# SolderingStation_Control.net
KiCad netlist of a schematic drawn in Altium Designer
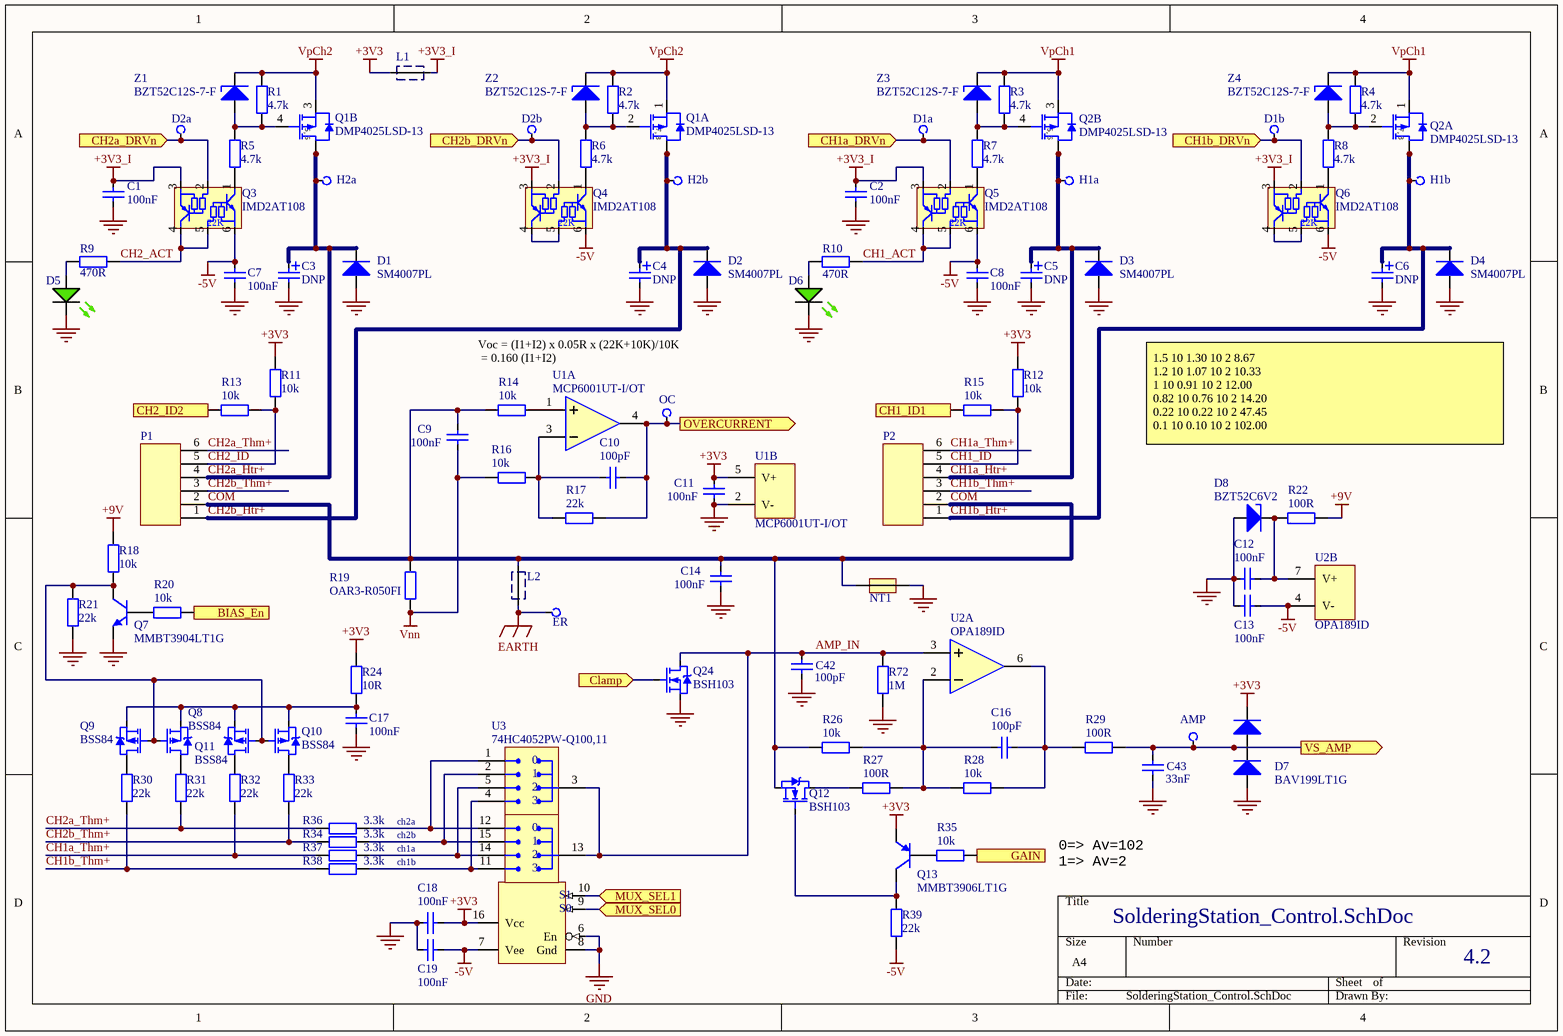
[diagram p0: SolderingStation_Control.SchDoc]

(export (version "E")
  (design (tool "Eeschema 10.0.6"))
  (components
    (comp (ref "AMP")
      (value "NTC1")
      (footprint "PCBPIN - 0.9mm")
      (description "Test Point")
      (libsource (lib "") (part "TP_1"))
    )
    (comp (ref "C1")
      (value "100nF")
      (footprint "CCNP1608-0603_N")
      (description "Capacitor non-polar SMT 0603")
      (fields
        (field (name "MANUFACTURER") "Generic Components")
        (field (name "PUBLISHER") "Altium Hobart Technology Centre")
      )
      (libsource (lib "MyLibrary") (part "Cap_CCNP_0603_100nF"))
    )
    (comp (ref "C2")
      (value "100nF")
      (footprint "CCNP1608-0603_N")
      (description "Capacitor non-polar SMT 0603")
      (fields
        (field (name "MANUFACTURER") "Generic Components")
        (field (name "PUBLISHER") "Altium Hobart Technology Centre")
      )
      (libsource (lib "MyLibrary") (part "Cap_CCNP_0603_100nF"))
    )
    (comp (ref "C3")
      (value "DNP")
      (footprint "CC2012-0805")
      (description "Capacitor SMT 0805")
      (fields
        (field (name "MANUFACTURER") "Generic Components")
        (field (name "PUBLISHER") "Altium Hobart Technology Centre")
      )
      (libsource (lib "MyLibrary") (part "Cap_CC_0805"))
    )
    (comp (ref "C4")
      (value "DNP")
      (footprint "CC2012-0805")
      (description "Capacitor SMT 0805")
      (fields
        (field (name "MANUFACTURER") "Generic Components")
        (field (name "PUBLISHER") "Altium Hobart Technology Centre")
      )
      (libsource (lib "MyLibrary") (part "Cap_CC_0805"))
    )
    (comp (ref "C5")
      (value "DNP")
      (footprint "CC2012-0805")
      (description "Capacitor SMT 0805")
      (fields
        (field (name "MANUFACTURER") "Generic Components")
        (field (name "PUBLISHER") "Altium Hobart Technology Centre")
      )
      (libsource (lib "MyLibrary") (part "Cap_CC_0805"))
    )
    (comp (ref "C6")
      (value "DNP")
      (footprint "CC2012-0805")
      (description "Capacitor SMT 0805")
      (fields
        (field (name "MANUFACTURER") "Generic Components")
        (field (name "PUBLISHER") "Altium Hobart Technology Centre")
      )
      (libsource (lib "MyLibrary") (part "Cap_CC_0805"))
    )
    (comp (ref "C7")
      (value "100nF")
      (footprint "CCNP1608-0603_N")
      (description "Capacitor non-polar SMT 0603")
      (fields
        (field (name "MANUFACTURER") "Generic Components")
        (field (name "PUBLISHER") "Altium Hobart Technology Centre")
      )
      (libsource (lib "MyLibrary") (part "Cap_CCNP_0603_100nF"))
    )
    (comp (ref "C8")
      (value "100nF")
      (footprint "CCNP1608-0603_N")
      (description "Capacitor non-polar SMT 0603")
      (fields
        (field (name "MANUFACTURER") "Generic Components")
        (field (name "PUBLISHER") "Altium Hobart Technology Centre")
      )
      (libsource (lib "MyLibrary") (part "Cap_CCNP_0603_100nF"))
    )
    (comp (ref "C9")
      (value "100nF")
      (footprint "CCNP1608-0603_N")
      (description "Capacitor non-polar SMT 0603")
      (fields
        (field (name "MANUFACTURER") "Generic Components")
        (field (name "PUBLISHER") "Altium Hobart Technology Centre")
      )
      (libsource (lib "MyLibrary") (part "Cap_CCNP_0603_100nF"))
    )
    (comp (ref "C10")
      (value "100pF")
      (footprint "CCNP1608-0603_N")
      (description "Capacitor non-polar SMT 0603")
      (fields
        (field (name "MANUFACTURER") "Generic Components")
        (field (name "PUBLISHER") "Altium Hobart Technology Centre")
      )
      (libsource (lib "MyLibrary") (part "Cap_CCNP_0603_100pF"))
    )
    (comp (ref "C11")
      (value "100nF")
      (footprint "CCNP1608-0603_N")
      (description "Capacitor non-polar SMT 0603")
      (fields
        (field (name "MANUFACTURER") "Generic Components")
        (field (name "PUBLISHER") "Altium Hobart Technology Centre")
      )
      (libsource (lib "MyLibrary") (part "Cap_CCNP_0603_100nF"))
    )
    (comp (ref "C12")
      (value "100nF")
      (footprint "CCNP1608-0603_N")
      (description "Capacitor non-polar SMT 0603")
      (fields
        (field (name "MANUFACTURER") "Generic Components")
        (field (name "PUBLISHER") "Altium Hobart Technology Centre")
      )
      (libsource (lib "MyLibrary") (part "Cap_CCNP_0603_100nF"))
    )
    (comp (ref "C13")
      (value "100nF")
      (footprint "CCNP1608-0603_N")
      (description "Capacitor non-polar SMT 0603")
      (fields
        (field (name "MANUFACTURER") "Generic Components")
        (field (name "PUBLISHER") "Altium Hobart Technology Centre")
      )
      (libsource (lib "MyLibrary") (part "Cap_CCNP_0603_100nF"))
    )
    (comp (ref "C14")
      (value "100nF")
      (footprint "CCNP1608-0603_N")
      (description "Capacitor non-polar SMT 0603")
      (fields
        (field (name "MANUFACTURER") "Generic Components")
        (field (name "PUBLISHER") "Altium Hobart Technology Centre")
      )
      (libsource (lib "MyLibrary") (part "Cap_CCNP_0603_100nF"))
    )
    (comp (ref "C16")
      (value "100pF")
      (footprint "CCNP1608-0603_N")
      (description "Capacitor non-polar SMT 0603")
      (fields
        (field (name "MANUFACTURER") "Generic Components")
        (field (name "PUBLISHER") "Altium Hobart Technology Centre")
      )
      (libsource (lib "MyLibrary") (part "Cap_CCNP_0603_100pF"))
    )
    (comp (ref "C17")
      (value "100nF")
      (footprint "CCNP1608-0603_N")
      (description "Capacitor non-polar SMT 0603")
      (fields
        (field (name "MANUFACTURER") "Generic Components")
        (field (name "PUBLISHER") "Altium Hobart Technology Centre")
      )
      (libsource (lib "MyLibrary") (part "Cap_CCNP_0603_100nF"))
    )
    (comp (ref "C18")
      (value "100nF")
      (footprint "CCNP1608-0603_N")
      (description "Capacitor non-polar SMT 0603")
      (fields
        (field (name "MANUFACTURER") "Generic Components")
        (field (name "PUBLISHER") "Altium Hobart Technology Centre")
      )
      (libsource (lib "MyLibrary") (part "Cap_CCNP_0603_100nF"))
    )
    (comp (ref "C19")
      (value "100nF")
      (footprint "CCNP1608-0603_N")
      (description "Capacitor non-polar SMT 0603")
      (fields
        (field (name "MANUFACTURER") "Generic Components")
        (field (name "PUBLISHER") "Altium Hobart Technology Centre")
      )
      (libsource (lib "MyLibrary") (part "Cap_CCNP_0603_100nF"))
    )
    (comp (ref "C42")
      (value "100pF")
      (footprint "CCNP1608-0603_N")
      (description "Capacitor non-polar SMT 0603")
      (fields
        (field (name "MANUFACTURER") "Generic Components")
        (field (name "PUBLISHER") "Altium Hobart Technology Centre")
      )
      (libsource (lib "MyLibrary") (part "Cap_CCNP_0603_100pF"))
    )
    (comp (ref "C43")
      (value "33nF")
      (footprint "CCNP1608-0603_N")
      (description "Capacitor non-polar SMT 0603")
      (fields
        (field (name "MANUFACTURER") "Generic Components")
        (field (name "PUBLISHER") "Altium Hobart Technology Centre")
      )
      (libsource (lib "MyLibrary") (part "Cap_CCNP_0603_100pF"))
    )
    (comp (ref "D1")
      (value "SM4007PL")
      (footprint "SOD-123FL")
      (description "Diodes - General Purpose, 1kV 1A 1.1V 1A SOD-123FL")
      (libsource (lib "MyLibrary") (part "SM4007PL"))
    )
    (comp (ref "D1a")
      (value "Drive1")
      (footprint "PCBPIN - 0.9mm")
      (description "Test Point")
      (libsource (lib "") (part "TP_1"))
    )
    (comp (ref "D1b")
      (value "Drive2")
      (footprint "PCBPIN - 0.9mm")
      (description "Test Point")
      (libsource (lib "") (part "TP_1"))
    )
    (comp (ref "D2")
      (value "SM4007PL")
      (footprint "SOD-123FL")
      (description "Diodes - General Purpose, 1kV 1A 1.1V 1A SOD-123FL")
      (libsource (lib "MyLibrary") (part "SM4007PL"))
    )
    (comp (ref "D2a")
      (value "Drive2")
      (footprint "PCBPIN - 0.9mm")
      (description "Test Point")
      (libsource (lib "") (part "TP_1"))
    )
    (comp (ref "D2b")
      (value "Drive2")
      (footprint "PCBPIN - 0.9mm")
      (description "Test Point")
      (libsource (lib "") (part "TP_1"))
    )
    (comp (ref "D3")
      (value "SM4007PL")
      (footprint "SOD-123FL")
      (description "Diodes - General Purpose, 1kV 1A 1.1V 1A SOD-123FL")
      (libsource (lib "MyLibrary") (part "SM4007PL"))
    )
    (comp (ref "D4")
      (value "SM4007PL")
      (footprint "SOD-123FL")
      (description "Diodes - General Purpose, 1kV 1A 1.1V 1A SOD-123FL")
      (libsource (lib "MyLibrary") (part "SM4007PL"))
    )
    (comp (ref "D5")
      (value "LED")
      (footprint "LED3MM-GREEN - 10mm Proud")
      (description "3mm Green LED")
      (fields (field (name "MANUFACTURER") "Generic Components") (field (name "PUBLISHER") "Altium Limited"))
      (libsource (lib "MySchLib") (part "LED_3MM_GREEN"))
    )
    (comp (ref "D6")
      (value "LED")
      (footprint "LED3MM-GREEN - 10mm Proud")
      (description "3mm Green LED")
      (fields (field (name "MANUFACTURER") "Generic Components") (field (name "PUBLISHER") "Altium Limited"))
      (libsource (lib "MySchLib") (part "LED_3MM_GREEN"))
    )
    (comp (ref "D7")
      (value "BAV199LT1G")
      (footprint "SOT23_N")
      (description "Diode - Dual Series low-leakage switching, SOT-23")
      (libsource (lib "MyLibrary") (part "BAV199LT1G"))
    )
    (comp (ref "D8")
      (value "BZT52C6V2")
      (footprint "SOD-123")
      (description "Zener Single Diode, 6.2 V, 500 mW, SOD-123, 6 %, 2 Pins, 150 °C")
      (fields (field (name "MANUFACTURER") "DiodesIncorporated"))
      (libsource (lib "MyLibrary") (part "BZT52C6V2"))
    )
    (comp (ref "ER")
      (value "Gnd")
      (footprint "PCBPIN - 0.9mm")
      (description "Test Point")
      (libsource (lib "MySchLib") (part "TP"))
    )
    (comp (ref "H1a")
      (value "Heater1")
      (footprint "PCBPIN - 0.9mm")
      (description "Test Point")
      (libsource (lib "MySchLib") (part "TP"))
    )
    (comp (ref "H1b")
      (value "Heater2")
      (footprint "PCBPIN - 0.9mm")
      (description "Test Point")
      (libsource (lib "MySchLib") (part "TP"))
    )
    (comp (ref "H2a")
      (value "Heater2")
      (footprint "PCBPIN - 0.9mm")
      (description "Test Point")
      (libsource (lib "MySchLib") (part "TP"))
    )
    (comp (ref "H2b")
      (value "Heater2")
      (footprint "PCBPIN - 0.9mm")
      (description "Test Point")
      (libsource (lib "MySchLib") (part "TP"))
    )
    (comp (ref "L1")
      (value "Ferrite Bead 600R@100MHz")
      (footprint "FB2012-0805")
      (description "Ferrite Bead 600Ω @ 100MHz 1 500mA 300mΩ 0805")
      (libsource (lib "MySchLib") (part "Ferrite Bead 0805 600R"))
    )
    (comp (ref "L2")
      (value "Ferrite Bead 600R@100MHz")
      (footprint "FB2012-0805")
      (description "Ferrite Bead 600Ω @ 100MHz 1 500mA 300mΩ 0805")
      (libsource (lib "MySchLib") (part "Ferrite Bead 0805 600R"))
    )
    (comp (ref "NT1")
      (value "NetTieVia")
      (footprint "NetTieVia")
      (libsource (lib "MyLibrary") (part "NetTieVia"))
    )
    (comp (ref "OC")
      (value "Overcurrent")
      (footprint "PCBPIN - 0.9mm")
      (description "Test Point")
      (libsource (lib "") (part "TP_1"))
    )
    (comp (ref "P1")
      (value "MOLEX-43045-0612")
      (footprint "MOLEX-43045-0612")
      (description "Wire-To-Board Connector, With Polarizing Peg, 3 mm, 6 Contacts, Header, Micro-Fit 3.0 43045 Series")
      (libsource (lib "MySchLib") (part "MOLEX-43045-0612"))
    )
    (comp (ref "P2")
      (value "MOLEX-43045-0612")
      (footprint "MOLEX-43045-0612")
      (description "Wire-To-Board Connector, With Polarizing Peg, 3 mm, 6 Contacts, Header, Micro-Fit 3.0 43045 Series")
      (libsource (lib "MySchLib") (part "MOLEX-43045-0612"))
    )
    (comp (ref "Q1")
      (value "DMP4025LSD-13")
      (footprint "SO-8_M")
      (description "P-Channel dual MOSFET, 40 V, 7.6 A, 0.018 ohm, SOIC, Surface Mount")
      (libsource (lib "MyLibrary") (part "DMP4025LSD-13"))
    )
    (comp (ref "Q2")
      (value "DMP4025LSD-13")
      (footprint "SO-8_M")
      (description "P-Channel dual MOSFET, 40 V, 7.6 A, 0.018 ohm, SOIC, Surface Mount")
      (libsource (lib "MyLibrary") (part "DMP4025LSD-13"))
    )
    (comp (ref "Q3")
      (value "IMD2AT108")
      (footprint "SOT457_M - MIRROR")
      (description "Pre-Biased NPN and PNP pair, 50 V, 100 mA, 22 kohm, 22 kohm")
      (libsource (lib "MySchLib") (part "IMD2AT108"))
    )
    (comp (ref "Q4")
      (value "IMD2AT108")
      (footprint "SOT457_M - MIRROR")
      (description "Pre-Biased NPN and PNP pair, 50 V, 100 mA, 22 kohm, 22 kohm")
      (libsource (lib "MySchLib") (part "IMD2AT108"))
    )
    (comp (ref "Q5")
      (value "IMD2AT108")
      (footprint "SOT457_M - MIRROR")
      (description "Pre-Biased NPN and PNP pair, 50 V, 100 mA, 22 kohm, 22 kohm")
      (libsource (lib "MySchLib") (part "IMD2AT108"))
    )
    (comp (ref "Q6")
      (value "IMD2AT108")
      (footprint "SOT457_M - MIRROR")
      (description "Pre-Biased NPN and PNP pair, 50 V, 100 mA, 22 kohm, 22 kohm")
      (libsource (lib "MySchLib") (part "IMD2AT108"))
    )
    (comp (ref "Q7")
      (value "MMBT3904LT1G")
      (footprint "SOT23_N")
      (description "General Purpose Transistor, NPN Silicon, 3-Pin SOT-23, Pb-Free, Tape and Reel")
      (fields (field (name "MANUFACTURER") "On Semiconductor"))
      (libsource (lib "MyLibrary") (part "MMBT3904LT1G"))
    )
    (comp (ref "Q8")
      (value "BSS84")
      (footprint "SOT23_M")
      (description "P-Channel Enhancement Mode FET -0.13 A, -50 V,  RDS(ON) = 10R at VGS = -5 V")
      (libsource (lib "MySchLib") (part "BSS84"))
    )
    (comp (ref "Q9")
      (value "BSS84")
      (footprint "SOT23_M")
      (description "P-Channel Enhancement Mode FET -0.13 A, -50 V,  RDS(ON) = 10R at VGS = -5 V")
      (libsource (lib "MySchLib") (part "BSS84"))
    )
    (comp (ref "Q10")
      (value "BSS84")
      (footprint "SOT23_M")
      (description "P-Channel Enhancement Mode FET -0.13 A, -50 V,  RDS(ON) = 10R at VGS = -5 V")
      (libsource (lib "MySchLib") (part "BSS84"))
    )
    (comp (ref "Q11")
      (value "BSS84")
      (footprint "SOT23_M")
      (description "P-Channel Enhancement Mode FET -0.13 A, -50 V,  RDS(ON) = 10R at VGS = -5 V")
      (libsource (lib "MySchLib") (part "BSS84"))
    )
    (comp (ref "Q12")
      (value "BSH103")
      (footprint "SOT23_N")
      (description "N-channel enhancement mode FET, , 30 V, 850 mA, 0.4 ohm, SOT23")
      (libsource (lib "MyLibrary") (part "BSH103"))
    )
    (comp (ref "Q13")
      (value "MMBT3906LT1G")
      (footprint "SOT23_N")
      (description "General Purpose Transistor, PNP Silicon, 3-Pin SOT-23, Pb-Free, Tape and Reel")
      (fields (field (name "MANUFACTURER") "On Semiconductor"))
      (libsource (lib "MyLibrary") (part "MMBT3906LT1G"))
    )
    (comp (ref "Q24")
      (value "BSH103")
      (footprint "SOT23_N")
      (description "N-channel enhancement mode FET, , 30 V, 850 mA, 0.4 ohm, SOT23")
      (libsource (lib "MyLibrary") (part "BSH103"))
    )
    (comp (ref "R1")
      (value "4.7k")
      (footprint "CR1608-0603_N")
      (description "Resistor SMT 0603")
      (fields
        (field (name "MANUFACTURER") "Generic Components")
        (field (name "PUBLISHER") "Altium Hobart Technology Centre")
      )
      (libsource (lib "MyLibrary") (part "Res_CR0603_4k7"))
    )
    (comp (ref "R2")
      (value "4.7k")
      (footprint "CR1608-0603_N")
      (description "Resistor SMT 0603")
      (fields
        (field (name "MANUFACTURER") "Generic Components")
        (field (name "PUBLISHER") "Altium Hobart Technology Centre")
      )
      (libsource (lib "MyLibrary") (part "Res_CR0603_4k7"))
    )
    (comp (ref "R3")
      (value "4.7k")
      (footprint "CR1608-0603_N")
      (description "Resistor SMT 0603")
      (fields
        (field (name "MANUFACTURER") "Generic Components")
        (field (name "PUBLISHER") "Altium Hobart Technology Centre")
      )
      (libsource (lib "MyLibrary") (part "Res_CR0603_4k7"))
    )
    (comp (ref "R4")
      (value "4.7k")
      (footprint "CR1608-0603_N")
      (description "Resistor SMT 0603")
      (fields
        (field (name "MANUFACTURER") "Generic Components")
        (field (name "PUBLISHER") "Altium Hobart Technology Centre")
      )
      (libsource (lib "MyLibrary") (part "Res_CR0603_4k7"))
    )
    (comp (ref "R5")
      (value "4.7k")
      (footprint "CR1608-0603_N")
      (description "Resistor SMT 0603")
      (fields
        (field (name "MANUFACTURER") "Generic Components")
        (field (name "PUBLISHER") "Altium Hobart Technology Centre")
      )
      (libsource (lib "MyLibrary") (part "Res_CR0603_4k7"))
    )
    (comp (ref "R6")
      (value "4.7k")
      (footprint "CR1608-0603_N")
      (description "Resistor SMT 0603")
      (fields
        (field (name "MANUFACTURER") "Generic Components")
        (field (name "PUBLISHER") "Altium Hobart Technology Centre")
      )
      (libsource (lib "MyLibrary") (part "Res_CR0603_4k7"))
    )
    (comp (ref "R7")
      (value "4.7k")
      (footprint "CR1608-0603_N")
      (description "Resistor SMT 0603")
      (fields
        (field (name "MANUFACTURER") "Generic Components")
        (field (name "PUBLISHER") "Altium Hobart Technology Centre")
      )
      (libsource (lib "MyLibrary") (part "Res_CR0603_4k7"))
    )
    (comp (ref "R8")
      (value "4.7k")
      (footprint "CR1608-0603_N")
      (description "Resistor SMT 0603")
      (fields
        (field (name "MANUFACTURER") "Generic Components")
        (field (name "PUBLISHER") "Altium Hobart Technology Centre")
      )
      (libsource (lib "MyLibrary") (part "Res_CR0603_4k7"))
    )
    (comp (ref "R9")
      (value "470R")
      (footprint "CR1608-0603_N")
      (description "Resistor SMT 0603")
      (fields
        (field (name "MANUFACTURER") "Generic Components")
        (field (name "PUBLISHER") "Altium Hobart Technology Centre")
      )
      (libsource (lib "MyLibrary") (part "Res_CR0603_470R"))
    )
    (comp (ref "R10")
      (value "470R")
      (footprint "CR1608-0603_N")
      (description "Resistor SMT 0603")
      (fields
        (field (name "MANUFACTURER") "Generic Components")
        (field (name "PUBLISHER") "Altium Hobart Technology Centre")
      )
      (libsource (lib "MyLibrary") (part "Res_CR0603_470R"))
    )
    (comp (ref "R11")
      (value "10k")
      (footprint "CR1608-0603_N")
      (description "Resistor SMT 0603")
      (fields
        (field (name "MANUFACTURER") "Generic Components")
        (field (name "PUBLISHER") "Altium Hobart Technology Centre")
      )
      (libsource (lib "") (part "Res_CR0603_10k_2"))
    )
    (comp (ref "R12")
      (value "10k")
      (footprint "CR1608-0603_N")
      (description "Resistor SMT 0603")
      (fields
        (field (name "MANUFACTURER") "Generic Components")
        (field (name "PUBLISHER") "Altium Hobart Technology Centre")
      )
      (libsource (lib "") (part "Res_CR0603_10k_2"))
    )
    (comp (ref "R13")
      (value "10k")
      (footprint "CR1608-0603_N")
      (description "Resistor SMT 0603")
      (fields
        (field (name "MANUFACTURER") "Generic Components")
        (field (name "PUBLISHER") "Altium Hobart Technology Centre")
      )
      (libsource (lib "") (part "Res_CR0603_10k_1"))
    )
    (comp (ref "R14")
      (value "10k")
      (footprint "CR1608-0603_N")
      (description "Resistor SMT 0603")
      (fields
        (field (name "MANUFACTURER") "Generic Components")
        (field (name "PUBLISHER") "Altium Hobart Technology Centre")
      )
      (libsource (lib "") (part "Res_CR0603_10k_3"))
    )
    (comp (ref "R15")
      (value "10k")
      (footprint "CR1608-0603_N")
      (description "Resistor SMT 0603")
      (fields
        (field (name "MANUFACTURER") "Generic Components")
        (field (name "PUBLISHER") "Altium Hobart Technology Centre")
      )
      (libsource (lib "") (part "Res_CR0603_10k_1"))
    )
    (comp (ref "R16")
      (value "10k")
      (footprint "CR1608-0603_N")
      (description "Resistor SMT 0603")
      (fields
        (field (name "MANUFACTURER") "Generic Components")
        (field (name "PUBLISHER") "Altium Hobart Technology Centre")
      )
      (libsource (lib "") (part "Res_CR0603_10k_3"))
    )
    (comp (ref "R17")
      (value "22k")
      (footprint "CR1608-0603_N")
      (description "Resistor SMT 0603")
      (fields
        (field (name "MANUFACTURER") "Generic Components")
        (field (name "PUBLISHER") "Altium Hobart Technology Centre")
      )
      (libsource (lib "MyLibrary") (part "Res_CR0603_22k"))
    )
    (comp (ref "R18")
      (value "10k")
      (footprint "CR1608-0603_N")
      (description "Resistor SMT 0603")
      (fields
        (field (name "MANUFACTURER") "Generic Components")
        (field (name "PUBLISHER") "Altium Hobart Technology Centre")
      )
      (libsource (lib "") (part "Res_CR0603_10k_1"))
    )
    (comp (ref "R19")
      (value "OAR3-R050FI")
      (footprint "OAR3-R050FI")
      (description "Current Sense Resistor, 0.05 ohm, OAR Series, 3 W, Metal Strip, Radial Leaded, 1%")
      (libsource (lib "MySchLib") (part "OAR3-R050FI"))
    )
    (comp (ref "R20")
      (value "10k")
      (footprint "CR1608-0603_N")
      (description "Resistor SMT 0603")
      (fields
        (field (name "MANUFACTURER") "Generic Components")
        (field (name "PUBLISHER") "Altium Hobart Technology Centre")
      )
      (libsource (lib "MyLibrary") (part "Res_CR0603_10k"))
    )
    (comp (ref "R21")
      (value "22k")
      (footprint "CR1608-0603_N")
      (description "Resistor SMT 0603")
      (fields
        (field (name "MANUFACTURER") "Generic Components")
        (field (name "PUBLISHER") "Altium Hobart Technology Centre")
      )
      (libsource (lib "") (part "Res_CR0603_22k_1"))
    )
    (comp (ref "R22")
      (value "100R")
      (footprint "CR1608-0603_N")
      (description "Resistor SMT 0603")
      (fields
        (field (name "MANUFACTURER") "Generic Components")
        (field (name "PUBLISHER") "Altium Hobart Technology Centre")
      )
      (libsource (lib "MyLibrary") (part "Res_CR0603_0R"))
    )
    (comp (ref "R24")
      (value "10R")
      (footprint "CR1608-0603_N")
      (description "Resistor SMT 0603")
      (fields
        (field (name "MANUFACTURER") "Generic Components")
        (field (name "PUBLISHER") "Altium Hobart Technology Centre")
      )
      (libsource (lib "MyLibrary") (part "Res_CR0603_10R"))
    )
    (comp (ref "R26")
      (value "10k")
      (footprint "CR1608-0603_N")
      (description "Resistor SMT 0603")
      (fields
        (field (name "MANUFACTURER") "Generic Components")
        (field (name "PUBLISHER") "Altium Hobart Technology Centre")
      )
      (libsource (lib "MyLibrary") (part "Res_CR0603_10k"))
    )
    (comp (ref "R27")
      (value "100R")
      (footprint "CR1608-0603_N")
      (description "Resistor SMT 0603")
      (fields
        (field (name "MANUFACTURER") "Generic Components")
        (field (name "PUBLISHER") "Altium Hobart Technology Centre")
      )
      (libsource (lib "MyLibrary") (part "Res_CR0603_3k3"))
    )
    (comp (ref "R28")
      (value "10k")
      (footprint "CR1608-0603_N")
      (description "Resistor SMT 0603")
      (fields
        (field (name "MANUFACTURER") "Generic Components")
        (field (name "PUBLISHER") "Altium Hobart Technology Centre")
      )
      (libsource (lib "MyLibrary") (part "Res_CR0603_10k"))
    )
    (comp (ref "R29")
      (value "100R")
      (footprint "CR1608-0603_N")
      (description "Resistor SMT 0603")
      (fields
        (field (name "MANUFACTURER") "Generic Components")
        (field (name "PUBLISHER") "Altium Hobart Technology Centre")
      )
      (libsource (lib "MyLibrary") (part "Res_CR0603_0R"))
    )
    (comp (ref "R30")
      (value "22k")
      (footprint "CR1608-0603_N")
      (description "Resistor SMT 0603")
      (fields
        (field (name "MANUFACTURER") "Generic Components")
        (field (name "PUBLISHER") "Altium Hobart Technology Centre")
      )
      (libsource (lib "MyLibrary") (part "Res_CR0603_22k"))
    )
    (comp (ref "R31")
      (value "22k")
      (footprint "CR1608-0603_N")
      (description "Resistor SMT 0603")
      (fields
        (field (name "MANUFACTURER") "Generic Components")
        (field (name "PUBLISHER") "Altium Hobart Technology Centre")
      )
      (libsource (lib "MyLibrary") (part "Res_CR0603_22k"))
    )
    (comp (ref "R32")
      (value "22k")
      (footprint "CR1608-0603_N")
      (description "Resistor SMT 0603")
      (fields
        (field (name "MANUFACTURER") "Generic Components")
        (field (name "PUBLISHER") "Altium Hobart Technology Centre")
      )
      (libsource (lib "") (part "Res_CR0603_22k_1"))
    )
    (comp (ref "R33")
      (value "22k")
      (footprint "CR1608-0603_N")
      (description "Resistor SMT 0603")
      (fields
        (field (name "MANUFACTURER") "Generic Components")
        (field (name "PUBLISHER") "Altium Hobart Technology Centre")
      )
      (libsource (lib "") (part "Res_CR0603_22k_1"))
    )
    (comp (ref "R34")
      (value "3.3k")
      (footprint "CR1608-0603_N")
      (description "Resistor SMT 0603")
      (fields
        (field (name "MANUFACTURER") "Generic Components")
        (field (name "PUBLISHER") "Altium Hobart Technology Centre")
      )
      (libsource (lib "MyLibrary") (part "Res_CR0603_3k3"))
    )
    (comp (ref "R35")
      (value "10k")
      (footprint "CR1608-0603_N")
      (description "Resistor SMT 0603")
      (fields
        (field (name "MANUFACTURER") "Generic Components")
        (field (name "PUBLISHER") "Altium Hobart Technology Centre")
      )
      (libsource (lib "MyLibrary") (part "Res_CR0603_10k"))
    )
    (comp (ref "R36")
      (value "3.3k")
      (footprint "CR1608-0603_N")
      (description "Resistor SMT 0603")
      (fields
        (field (name "MANUFACTURER") "Generic Components")
        (field (name "PUBLISHER") "Altium Hobart Technology Centre")
      )
      (libsource (lib "MyLibrary") (part "Res_CR0603_3k3"))
    )
    (comp (ref "R37")
      (value "3.3k")
      (footprint "CR1608-0603_N")
      (description "Resistor SMT 0603")
      (fields
        (field (name "MANUFACTURER") "Generic Components")
        (field (name "PUBLISHER") "Altium Hobart Technology Centre")
      )
      (libsource (lib "MyLibrary") (part "Res_CR0603_3k3"))
    )
    (comp (ref "R38")
      (value "3.3k")
      (footprint "CR1608-0603_N")
      (description "Resistor SMT 0603")
      (fields
        (field (name "MANUFACTURER") "Generic Components")
        (field (name "PUBLISHER") "Altium Hobart Technology Centre")
      )
      (libsource (lib "MyLibrary") (part "Res_CR0603_3k3"))
    )
    (comp (ref "R39")
      (value "22k")
      (footprint "CR1608-0603_N")
      (description "Resistor SMT 0603")
      (fields
        (field (name "MANUFACTURER") "Generic Components")
        (field (name "PUBLISHER") "Altium Hobart Technology Centre")
      )
      (libsource (lib "") (part "Res_CR0603_22k_1"))
    )
    (comp (ref "R72")
      (value "1M")
      (footprint "CR1608-0603_N")
      (description "Resistor SMT 0603")
      (fields
        (field (name "MANUFACTURER") "Generic Components")
        (field (name "PUBLISHER") "Altium Hobart Technology Centre")
      )
      (libsource (lib "MyLibrary") (part "Res_CR0603_1M"))
    )
    (comp (ref "U1")
      (value "MCP6001UT-I/OT")
      (footprint "SOT23-5_M")
      (description "Op-Amp, Single supply R-R in/out")
      (libsource (lib "MySchLib") (part "MCP6001UT-I/OT"))
    )
    (comp (ref "U2")
      (value "OPA189ID")
      (footprint "SOIC127P600-8N")
      (description "Op-Amp 14MHz, MUX-friendly, low-noise, Zero-Drift, RRO, CMOS precision")
      (libsource (lib "MySchLib") (part "OPA189ID"))
    )
    (comp (ref "U3")
      (value "74HC4052PW-Q100,11")
      (footprint "TSSOP16_M")
      (description "Analog Multiplexer / Demultiplexer, 4:1, 2 Circuits, 225 ohm, 2V to 10V, TSSOP-16")
      (libsource (lib "MySchLib") (part "74HC4052PW-Q100,11"))
    )
    (comp (ref "Z1")
      (value "BZT52C12S-7-F")
      (footprint "SOD-323")
      (description "Surface Mount Zener Diode, 12-13 V, -65 to 150 degC, SOD-123")
      (libsource (lib "MySchLib") (part "BZT52C12S-7-F"))
    )
    (comp (ref "Z2")
      (value "BZT52C12S-7-F")
      (footprint "SOD-323")
      (description "Surface Mount Zener Diode, 12-13 V, -65 to 150 degC, SOD-123")
      (libsource (lib "MySchLib") (part "BZT52C12S-7-F"))
    )
    (comp (ref "Z3")
      (value "BZT52C12S-7-F")
      (footprint "SOD-323")
      (description "Surface Mount Zener Diode, 12-13 V, -65 to 150 degC, SOD-123")
      (libsource (lib "MySchLib") (part "BZT52C12S-7-F"))
    )
    (comp (ref "Z4")
      (value "BZT52C12S-7-F")
      (footprint "SOD-323")
      (description "Surface Mount Zener Diode, 12-13 V, -65 to 150 degC, SOD-123")
      (libsource (lib "MySchLib") (part "BZT52C12S-7-F"))
    )
  )
  (nets
    (net (code "1") (name "+3V3") (class "Default")
      (node (ref "C11") (pin "1") (pinfunction "1_1") (pintype "passive"))
      (node (ref "C18") (pin "1") (pinfunction "1_1") (pintype "passive"))
      (node (ref "D7") (pin "2") (pinfunction "A2_2") (pintype "passive"))
      (node (ref "L1") (pin "1") (pinfunction "1_1") (pintype "passive"))
      (node (ref "Q13") (pin "2") (pinfunction "E_2") (pintype "passive"))
      (node (ref "R11") (pin "2") (pinfunction "2_2") (pintype "passive"))
      (node (ref "R12") (pin "2") (pinfunction "2_2") (pintype "passive"))
      (node (ref "R24") (pin "1") (pinfunction "1_1") (pintype "passive"))
      (node (ref "U1") (pin "5") (pinfunction "V+_5") (pintype "power_in"))
      (node (ref "U3") (pin "16") (pinfunction "Vcc_16") (pintype "power_in"))
    )
    (net (code "2") (name "+3V3_I") (class "Default")
      (node (ref "C1") (pin "1") (pinfunction "1_1") (pintype "passive"))
      (node (ref "C2") (pin "1") (pinfunction "1_1") (pintype "passive"))
      (node (ref "L1") (pin "2") (pinfunction "2_2") (pintype "passive"))
      (node (ref "Q3") (pin "3") (pinfunction "E2_3") (pintype "passive"))
      (node (ref "Q4") (pin "3") (pinfunction "E2_3") (pintype "passive"))
      (node (ref "Q5") (pin "3") (pinfunction "E2_3") (pintype "passive"))
      (node (ref "Q6") (pin "3") (pinfunction "E2_3") (pintype "passive"))
    )
    (net (code "3") (name "+9V") (class "Default")
      (node (ref "R18") (pin "1") (pinfunction "1_1") (pintype "passive"))
      (node (ref "R22") (pin "1") (pinfunction "1_1") (pintype "passive"))
    )
    (net (code "4") (name "-5V") (class "Default")
      (node (ref "C13") (pin "1") (pinfunction "1_1") (pintype "passive"))
      (node (ref "C19") (pin "1") (pinfunction "1_1") (pintype "passive"))
      (node (ref "C7") (pin "1") (pinfunction "1_1") (pintype "passive"))
      (node (ref "C8") (pin "1") (pinfunction "1_1") (pintype "passive"))
      (node (ref "Q3") (pin "6") (pinfunction "E1_6") (pintype "passive"))
      (node (ref "Q4") (pin "6") (pinfunction "E1_6") (pintype "passive"))
      (node (ref "Q5") (pin "6") (pinfunction "E1_6") (pintype "passive"))
      (node (ref "Q6") (pin "6") (pinfunction "E1_6") (pintype "passive"))
      (node (ref "R39") (pin "1") (pinfunction "1_1") (pintype "passive"))
      (node (ref "U2") (pin "4") (pinfunction "V-_4") (pintype "power_in"))
      (node (ref "U3") (pin "7") (pinfunction "Vee_7") (pintype "power_in"))
    )
    (net (code "5") (name "/AMP_IN") (class "Default")
      (node (ref "C42") (pin "2") (pinfunction "2_2") (pintype "passive"))
      (node (ref "Q24") (pin "3") (pinfunction "D_3") (pintype "passive"))
      (node (ref "R72") (pin "2") (pinfunction "2_2") (pintype "passive"))
      (node (ref "U2") (pin "3") (pinfunction "+IN_3") (pintype "passive"))
      (node (ref "U3") (pin "13") (pinfunction "1Z_13") (pintype "passive"))
      (node (ref "U3") (pin "3") (pinfunction "2Z_3") (pintype "passive"))
    )
    (net (code "6") (name "/BIAS_En") (class "Default")
      (node (ref "R20") (pin "2") (pinfunction "2_2") (pintype "passive"))
    )
    (net (code "7") (name "/CH1_ACT") (class "Default")
      (node (ref "Q5") (pin "4") (pinfunction "C2_4") (pintype "passive"))
      (node (ref "Q5") (pin "5") (pinfunction "B1_5") (pintype "passive"))
      (node (ref "R10") (pin "2") (pinfunction "2_2") (pintype "passive"))
    )
    (net (code "8") (name "/CH1_ID") (class "Default")
      (node (ref "P2") (pin "5") (pinfunction "5_5") (pintype "passive"))
      (node (ref "R12") (pin "1") (pinfunction "1_1") (pintype "passive"))
      (node (ref "R15") (pin "1") (pinfunction "1_1") (pintype "passive"))
    )
    (net (code "9") (name "/CH1_ID1") (class "Default")
      (node (ref "R15") (pin "2") (pinfunction "2_2") (pintype "passive"))
    )
    (net (code "10") (name "/CH1a_DRVn") (class "Default")
      (node (ref "D1a") (pin "1") (pinfunction "TP_1") (pintype "passive"))
      (node (ref "Q5") (pin "2") (pinfunction "B2_2") (pintype "passive"))
    )
    (net (code "11") (name "/CH1a_Htr+") (class "Default")
      (node (ref "C5") (pin "1") (pinfunction "1_1") (pintype "passive"))
      (node (ref "D3") (pin "K") (pinfunction "K_K") (pintype "passive"))
      (node (ref "H1a") (pin "1") (pinfunction "TP_1") (pintype "passive"))
      (node (ref "P2") (pin "4") (pinfunction "4_4") (pintype "passive"))
      (node (ref "Q2") (pin "5") (pinfunction "D2_5") (pintype "passive"))
      (node (ref "Q2") (pin "6") (pinfunction "D2_6") (pintype "passive"))
    )
    (net (code "12") (name "/CH1a_Thm+") (class "Default")
      (node (ref "P2") (pin "6") (pinfunction "6_6") (pintype "passive"))
      (node (ref "R32") (pin "1") (pinfunction "1_1") (pintype "passive"))
      (node (ref "R37") (pin "2") (pinfunction "2_2") (pintype "passive"))
    )
    (net (code "13") (name "/CH1b_DRVn") (class "Default")
      (node (ref "D1b") (pin "1") (pinfunction "TP_1") (pintype "passive"))
      (node (ref "Q6") (pin "2") (pinfunction "B2_2") (pintype "passive"))
    )
    (net (code "14") (name "/CH1b_Htr+") (class "Default")
      (node (ref "C6") (pin "1") (pinfunction "1_1") (pintype "passive"))
      (node (ref "D4") (pin "K") (pinfunction "K_K") (pintype "passive"))
      (node (ref "H1b") (pin "1") (pinfunction "TP_1") (pintype "passive"))
      (node (ref "P2") (pin "1") (pinfunction "1_1") (pintype "passive"))
      (node (ref "Q2") (pin "7") (pinfunction "D1_7") (pintype "passive"))
      (node (ref "Q2") (pin "8") (pinfunction "D1_8") (pintype "passive"))
    )
    (net (code "15") (name "/CH1b_Thm+") (class "Default")
      (node (ref "P2") (pin "3") (pinfunction "3_3") (pintype "passive"))
      (node (ref "R30") (pin "1") (pinfunction "1_1") (pintype "passive"))
      (node (ref "R38") (pin "2") (pinfunction "2_2") (pintype "passive"))
    )
    (net (code "16") (name "/CH2_ACT") (class "Default")
      (node (ref "Q3") (pin "4") (pinfunction "C2_4") (pintype "passive"))
      (node (ref "Q3") (pin "5") (pinfunction "B1_5") (pintype "passive"))
      (node (ref "R9") (pin "2") (pinfunction "2_2") (pintype "passive"))
    )
    (net (code "17") (name "/CH2_ID") (class "Default")
      (node (ref "P1") (pin "5") (pinfunction "5_5") (pintype "passive"))
      (node (ref "R11") (pin "1") (pinfunction "1_1") (pintype "passive"))
      (node (ref "R13") (pin "1") (pinfunction "1_1") (pintype "passive"))
    )
    (net (code "18") (name "/CH2_ID2") (class "Default")
      (node (ref "R13") (pin "2") (pinfunction "2_2") (pintype "passive"))
    )
    (net (code "19") (name "/CH2a_DRVn") (class "Default")
      (node (ref "D2a") (pin "1") (pinfunction "TP_1") (pintype "passive"))
      (node (ref "Q3") (pin "2") (pinfunction "B2_2") (pintype "passive"))
    )
    (net (code "20") (name "/CH2a_Htr+") (class "Default")
      (node (ref "C3") (pin "1") (pinfunction "1_1") (pintype "passive"))
      (node (ref "D1") (pin "K") (pinfunction "K_K") (pintype "passive"))
      (node (ref "H2a") (pin "1") (pinfunction "TP_1") (pintype "passive"))
      (node (ref "P1") (pin "4") (pinfunction "4_4") (pintype "passive"))
      (node (ref "Q1") (pin "5") (pinfunction "D2_5") (pintype "passive"))
      (node (ref "Q1") (pin "6") (pinfunction "D2_6") (pintype "passive"))
    )
    (net (code "21") (name "/CH2a_Thm+") (class "Default")
      (node (ref "P1") (pin "6") (pinfunction "6_6") (pintype "passive"))
      (node (ref "R31") (pin "1") (pinfunction "1_1") (pintype "passive"))
      (node (ref "R36") (pin "2") (pinfunction "2_2") (pintype "passive"))
    )
    (net (code "22") (name "/CH2b_DRVn") (class "Default")
      (node (ref "D2b") (pin "1") (pinfunction "TP_1") (pintype "passive"))
      (node (ref "Q4") (pin "2") (pinfunction "B2_2") (pintype "passive"))
    )
    (net (code "23") (name "/CH2b_Htr+") (class "Default")
      (node (ref "C4") (pin "1") (pinfunction "1_1") (pintype "passive"))
      (node (ref "D2") (pin "K") (pinfunction "K_K") (pintype "passive"))
      (node (ref "H2b") (pin "1") (pinfunction "TP_1") (pintype "passive"))
      (node (ref "P1") (pin "1") (pinfunction "1_1") (pintype "passive"))
      (node (ref "Q1") (pin "7") (pinfunction "D1_7") (pintype "passive"))
      (node (ref "Q1") (pin "8") (pinfunction "D1_8") (pintype "passive"))
    )
    (net (code "24") (name "/CH2b_Thm+") (class "Default")
      (node (ref "P1") (pin "3") (pinfunction "3_3") (pintype "passive"))
      (node (ref "R33") (pin "1") (pinfunction "1_1") (pintype "passive"))
      (node (ref "R34") (pin "2") (pinfunction "2_2") (pintype "passive"))
    )
    (net (code "25") (name "/COM") (class "Default")
      (node (ref "C14") (pin "1") (pinfunction "1_1") (pintype "passive"))
      (node (ref "C9") (pin "1") (pinfunction "1_1") (pintype "passive"))
      (node (ref "L2") (pin "2") (pinfunction "2_2") (pintype "passive"))
      (node (ref "NT1") (pin "2") (pinfunction "2_2") (pintype "passive"))
      (node (ref "P1") (pin "2") (pinfunction "2_2") (pintype "passive"))
      (node (ref "P2") (pin "2") (pinfunction "2_2") (pintype "passive"))
      (node (ref "Q12") (pin "2") (pinfunction "S_2") (pintype "passive"))
      (node (ref "R14") (pin "2") (pinfunction "2_2") (pintype "passive"))
      (node (ref "R19") (pin "2") (pinfunction "2_2") (pintype "passive"))
      (node (ref "R26") (pin "1") (pinfunction "1_1") (pintype "passive"))
    )
    (net (code "26") (name "/Clamp") (class "Default")
      (node (ref "Q24") (pin "1") (pinfunction "G_1") (pintype "passive"))
    )
    (net (code "27") (name "/GAIN") (class "Default")
      (node (ref "R35") (pin "2") (pinfunction "2_2") (pintype "passive"))
    )
    (net (code "28") (name "/MUX_SEL0") (class "Default")
      (node (ref "U3") (pin "9") (pinfunction "S1_9") (pintype "input"))
    )
    (net (code "29") (name "/MUX_SEL1") (class "Default")
      (node (ref "U3") (pin "10") (pinfunction "S0_10") (pintype "input"))
    )
    (net (code "30") (name "/OVERCURRENT") (class "Default")
      (node (ref "C10") (pin "2") (pinfunction "2_2") (pintype "passive"))
      (node (ref "OC") (pin "1") (pinfunction "TP_1") (pintype "passive"))
      (node (ref "R17") (pin "2") (pinfunction "2_2") (pintype "passive"))
      (node (ref "U1") (pin "4") (pinfunction "Out_4") (pintype "passive"))
    )
    (net (code "31") (name "/VS_AMP") (class "Default")
      (node (ref "AMP") (pin "1") (pinfunction "TP_1") (pintype "passive"))
      (node (ref "C43") (pin "2") (pinfunction "2_2") (pintype "passive"))
      (node (ref "D7") (pin "3") (pinfunction "K_3") (pintype "passive"))
      (node (ref "R29") (pin "1") (pinfunction "1_1") (pintype "passive"))
    )
    (net (code "32") (name "EARTH") (class "Default")
      (node (ref "ER") (pin "1") (pinfunction "TP_1") (pintype "passive"))
      (node (ref "L2") (pin "1") (pinfunction "1_1") (pintype "passive"))
    )
    (net (code "33") (name "GND") (class "Default")
      (node (ref "C1") (pin "2") (pinfunction "2_2") (pintype "passive"))
      (node (ref "C11") (pin "2") (pinfunction "2_2") (pintype "passive"))
      (node (ref "C12") (pin "2") (pinfunction "2_2") (pintype "passive"))
      (node (ref "C13") (pin "2") (pinfunction "2_2") (pintype "passive"))
      (node (ref "C14") (pin "2") (pinfunction "2_2") (pintype "passive"))
      (node (ref "C17") (pin "1") (pinfunction "1_1") (pintype "passive"))
      (node (ref "C18") (pin "2") (pinfunction "2_2") (pintype "passive"))
      (node (ref "C19") (pin "2") (pinfunction "2_2") (pintype "passive"))
      (node (ref "C2") (pin "2") (pinfunction "2_2") (pintype "passive"))
      (node (ref "C3") (pin "2") (pinfunction "2_2") (pintype "passive"))
      (node (ref "C4") (pin "2") (pinfunction "2_2") (pintype "passive"))
      (node (ref "C42") (pin "1") (pinfunction "1_1") (pintype "passive"))
      (node (ref "C43") (pin "1") (pinfunction "1_1") (pintype "passive"))
      (node (ref "C5") (pin "2") (pinfunction "2_2") (pintype "passive"))
      (node (ref "C6") (pin "2") (pinfunction "2_2") (pintype "passive"))
      (node (ref "C7") (pin "2") (pinfunction "2_2") (pintype "passive"))
      (node (ref "C8") (pin "2") (pinfunction "2_2") (pintype "passive"))
      (node (ref "D1") (pin "A") (pinfunction "A_A") (pintype "passive"))
      (node (ref "D2") (pin "A") (pinfunction "A_A") (pintype "passive"))
      (node (ref "D3") (pin "A") (pinfunction "A_A") (pintype "passive"))
      (node (ref "D4") (pin "A") (pinfunction "A_A") (pintype "passive"))
      (node (ref "D5") (pin "K") (pinfunction "K_K") (pintype "passive"))
      (node (ref "D6") (pin "K") (pinfunction "K_K") (pintype "passive"))
      (node (ref "D7") (pin "1") (pinfunction "A1_1") (pintype "passive"))
      (node (ref "D8") (pin "A") (pinfunction "A_A") (pintype "passive"))
      (node (ref "NT1") (pin "1") (pinfunction "1_1") (pintype "passive"))
      (node (ref "Q24") (pin "2") (pinfunction "S_2") (pintype "passive"))
      (node (ref "Q7") (pin "2") (pinfunction "E_2") (pintype "passive"))
      (node (ref "R21") (pin "1") (pinfunction "1_1") (pintype "passive"))
      (node (ref "R72") (pin "1") (pinfunction "1_1") (pintype "passive"))
      (node (ref "U1") (pin "2") (pinfunction "V-_2") (pintype "power_in"))
      (node (ref "U3") (pin "6") (pinfunction "En_6") (pintype "input"))
      (node (ref "U3") (pin "8") (pinfunction "Gnd_8") (pintype "power_in"))
    )
    (net (code "34") (name "Net-(D5-PadA)") (class "Default")
      (node (ref "D5") (pin "A") (pinfunction "A_A") (pintype "passive"))
      (node (ref "R9") (pin "1") (pinfunction "1_1") (pintype "passive"))
    )
    (net (code "35") (name "Net-(D6-PadA)") (class "Default")
      (node (ref "D6") (pin "A") (pinfunction "A_A") (pintype "passive"))
      (node (ref "R10") (pin "1") (pinfunction "1_1") (pintype "passive"))
    )
    (net (code "36") (name "Net-(Q1A-G1)") (class "Default")
      (node (ref "Q1") (pin "2") (pinfunction "G1_2") (pintype "passive"))
      (node (ref "R2") (pin "1") (pinfunction "1_1") (pintype "passive"))
      (node (ref "R6") (pin "2") (pinfunction "2_2") (pintype "passive"))
      (node (ref "Z2") (pin "A") (pinfunction "A_A") (pintype "passive"))
    )
    (net (code "37") (name "Net-(Q1B-G2)") (class "Default")
      (node (ref "Q1") (pin "4") (pinfunction "G2_4") (pintype "passive"))
      (node (ref "R1") (pin "1") (pinfunction "1_1") (pintype "passive"))
      (node (ref "R5") (pin "2") (pinfunction "2_2") (pintype "passive"))
      (node (ref "Z1") (pin "A") (pinfunction "A_A") (pintype "passive"))
    )
    (net (code "38") (name "Net-(Q2A-G1)") (class "Default")
      (node (ref "Q2") (pin "2") (pinfunction "G1_2") (pintype "passive"))
      (node (ref "R4") (pin "1") (pinfunction "1_1") (pintype "passive"))
      (node (ref "R8") (pin "2") (pinfunction "2_2") (pintype "passive"))
      (node (ref "Z4") (pin "A") (pinfunction "A_A") (pintype "passive"))
    )
    (net (code "39") (name "Net-(Q2B-G2)") (class "Default")
      (node (ref "Q2") (pin "4") (pinfunction "G2_4") (pintype "passive"))
      (node (ref "R3") (pin "1") (pinfunction "1_1") (pintype "passive"))
      (node (ref "R7") (pin "2") (pinfunction "2_2") (pintype "passive"))
      (node (ref "Z3") (pin "A") (pinfunction "A_A") (pintype "passive"))
    )
    (net (code "40") (name "Net-(Q3-C1)") (class "Default")
      (node (ref "Q3") (pin "1") (pinfunction "C1_1") (pintype "passive"))
      (node (ref "R5") (pin "1") (pinfunction "1_1") (pintype "passive"))
    )
    (net (code "41") (name "Net-(Q4-B1)") (class "Default")
      (node (ref "Q4") (pin "4") (pinfunction "C2_4") (pintype "passive"))
      (node (ref "Q4") (pin "5") (pinfunction "B1_5") (pintype "passive"))
    )
    (net (code "42") (name "Net-(Q4-C1)") (class "Default")
      (node (ref "Q4") (pin "1") (pinfunction "C1_1") (pintype "passive"))
      (node (ref "R6") (pin "1") (pinfunction "1_1") (pintype "passive"))
    )
    (net (code "43") (name "Net-(Q5-C1)") (class "Default")
      (node (ref "Q5") (pin "1") (pinfunction "C1_1") (pintype "passive"))
      (node (ref "R7") (pin "1") (pinfunction "1_1") (pintype "passive"))
    )
    (net (code "44") (name "Net-(Q6-B1)") (class "Default")
      (node (ref "Q6") (pin "4") (pinfunction "C2_4") (pintype "passive"))
      (node (ref "Q6") (pin "5") (pinfunction "B1_5") (pintype "passive"))
    )
    (net (code "45") (name "Net-(Q6-C1)") (class "Default")
      (node (ref "Q6") (pin "1") (pinfunction "C1_1") (pintype "passive"))
      (node (ref "R8") (pin "1") (pinfunction "1_1") (pintype "passive"))
    )
    (net (code "46") (name "Net-(Q7-B)") (class "Default")
      (node (ref "Q7") (pin "1") (pinfunction "B_1") (pintype "passive"))
      (node (ref "R20") (pin "1") (pinfunction "1_1") (pintype "passive"))
    )
    (net (code "47") (name "Net-(Q8-D)") (class "Default")
      (node (ref "Q8") (pin "3") (pinfunction "D_3") (pintype "passive"))
      (node (ref "R32") (pin "2") (pinfunction "2_2") (pintype "passive"))
    )
    (net (code "48") (name "Net-(Q9-D)") (class "Default")
      (node (ref "Q9") (pin "3") (pinfunction "D_3") (pintype "passive"))
      (node (ref "R30") (pin "2") (pinfunction "2_2") (pintype "passive"))
    )
    (net (code "49") (name "Net-(Q10-D)") (class "Default")
      (node (ref "Q10") (pin "3") (pinfunction "D_3") (pintype "passive"))
      (node (ref "R33") (pin "2") (pinfunction "2_2") (pintype "passive"))
    )
    (net (code "50") (name "Net-(Q10-G)") (class "Default")
      (node (ref "Q10") (pin "1") (pinfunction "G_1") (pintype "passive"))
      (node (ref "Q11") (pin "1") (pinfunction "G_1") (pintype "passive"))
      (node (ref "Q7") (pin "3") (pinfunction "C_3") (pintype "passive"))
      (node (ref "Q8") (pin "1") (pinfunction "G_1") (pintype "passive"))
      (node (ref "Q9") (pin "1") (pinfunction "G_1") (pintype "passive"))
      (node (ref "R18") (pin "2") (pinfunction "2_2") (pintype "passive"))
      (node (ref "R21") (pin "2") (pinfunction "2_2") (pintype "passive"))
    )
    (net (code "51") (name "Net-(Q10-S)") (class "Default")
      (node (ref "C17") (pin "2") (pinfunction "2_2") (pintype "passive"))
      (node (ref "Q10") (pin "2") (pinfunction "S_2") (pintype "passive"))
      (node (ref "Q11") (pin "2") (pinfunction "S_2") (pintype "passive"))
      (node (ref "Q8") (pin "2") (pinfunction "S_2") (pintype "passive"))
      (node (ref "Q9") (pin "2") (pinfunction "S_2") (pintype "passive"))
      (node (ref "R24") (pin "2") (pinfunction "2_2") (pintype "passive"))
    )
    (net (code "52") (name "Net-(Q11-D)") (class "Default")
      (node (ref "Q11") (pin "3") (pinfunction "D_3") (pintype "passive"))
      (node (ref "R31") (pin "2") (pinfunction "2_2") (pintype "passive"))
    )
    (net (code "53") (name "Net-(Q12-D)") (class "Default")
      (node (ref "Q12") (pin "3") (pinfunction "D_3") (pintype "passive"))
      (node (ref "R27") (pin "2") (pinfunction "2_2") (pintype "passive"))
    )
    (net (code "54") (name "Net-(Q12-G)") (class "Default")
      (node (ref "Q12") (pin "1") (pinfunction "G_1") (pintype "passive"))
      (node (ref "Q13") (pin "3") (pinfunction "C_3") (pintype "passive"))
      (node (ref "R39") (pin "2") (pinfunction "2_2") (pintype "passive"))
    )
    (net (code "55") (name "Net-(Q13-B)") (class "Default")
      (node (ref "Q13") (pin "1") (pinfunction "B_1") (pintype "passive"))
      (node (ref "R35") (pin "1") (pinfunction "1_1") (pintype "passive"))
    )
    (net (code "56") (name "Net-(U1A-In+)") (class "Default")
      (node (ref "R14") (pin "1") (pinfunction "1_1") (pintype "passive"))
      (node (ref "U1") (pin "1") (pinfunction "In+_1") (pintype "passive"))
    )
    (net (code "57") (name "Net-(U1A-In-)") (class "Default")
      (node (ref "C10") (pin "1") (pinfunction "1_1") (pintype "passive"))
      (node (ref "R16") (pin "1") (pinfunction "1_1") (pintype "passive"))
      (node (ref "R17") (pin "1") (pinfunction "1_1") (pintype "passive"))
      (node (ref "U1") (pin "3") (pinfunction "In-_3") (pintype "passive"))
    )
    (net (code "58") (name "Net-(U2A--IN)") (class "Default")
      (node (ref "C16") (pin "1") (pinfunction "1_1") (pintype "passive"))
      (node (ref "R26") (pin "2") (pinfunction "2_2") (pintype "passive"))
      (node (ref "R27") (pin "1") (pinfunction "1_1") (pintype "passive"))
      (node (ref "R28") (pin "1") (pinfunction "1_1") (pintype "passive"))
      (node (ref "U2") (pin "2") (pinfunction "-IN_2") (pintype "passive"))
    )
    (net (code "59") (name "Net-(U2A-OUT)") (class "Default")
      (node (ref "C16") (pin "2") (pinfunction "2_2") (pintype "passive"))
      (node (ref "R28") (pin "2") (pinfunction "2_2") (pintype "passive"))
      (node (ref "R29") (pin "2") (pinfunction "2_2") (pintype "passive"))
      (node (ref "U2") (pin "6") (pinfunction "OUT_6") (pintype "passive"))
    )
    (net (code "60") (name "Net-(U2B-V+)") (class "Default")
      (node (ref "C12") (pin "1") (pinfunction "1_1") (pintype "passive"))
      (node (ref "D8") (pin "K") (pinfunction "K_K") (pintype "passive"))
      (node (ref "R22") (pin "2") (pinfunction "2_2") (pintype "passive"))
      (node (ref "U2") (pin "7") (pinfunction "V+_7") (pintype "power_in"))
    )
    (net (code "61") (name "Net-(U3-1Y0)") (class "Default")
      (node (ref "R36") (pin "1") (pinfunction "1_1") (pintype "passive"))
      (node (ref "U3") (pin "1") (pinfunction "2Y0_1") (pintype "passive"))
      (node (ref "U3") (pin "12") (pinfunction "1Y0_12") (pintype "passive"))
    )
    (net (code "62") (name "Net-(U3-1Y1)") (class "Default")
      (node (ref "R37") (pin "1") (pinfunction "1_1") (pintype "passive"))
      (node (ref "U3") (pin "14") (pinfunction "1Y1_14") (pintype "passive"))
      (node (ref "U3") (pin "5") (pinfunction "2Y1_5") (pintype "passive"))
    )
    (net (code "63") (name "Net-(U3-1Y2)") (class "Default")
      (node (ref "R34") (pin "1") (pinfunction "1_1") (pintype "passive"))
      (node (ref "U3") (pin "15") (pinfunction "1Y2_15") (pintype "passive"))
      (node (ref "U3") (pin "2") (pinfunction "2Y2_2") (pintype "passive"))
    )
    (net (code "64") (name "Net-(U3-1Y3)") (class "Default")
      (node (ref "R38") (pin "1") (pinfunction "1_1") (pintype "passive"))
      (node (ref "U3") (pin "11") (pinfunction "1Y3_11") (pintype "passive"))
      (node (ref "U3") (pin "4") (pinfunction "2Y3_4") (pintype "passive"))
    )
    (net (code "65") (name "Vnn") (class "Default")
      (node (ref "C9") (pin "2") (pinfunction "2_2") (pintype "passive"))
      (node (ref "R16") (pin "2") (pinfunction "2_2") (pintype "passive"))
      (node (ref "R19") (pin "1") (pinfunction "1_1") (pintype "passive"))
    )
    (net (code "66") (name "VpCh1") (class "Default")
      (node (ref "Q2") (pin "1") (pinfunction "S1_1") (pintype "passive"))
      (node (ref "Q2") (pin "3") (pinfunction "S2_3") (pintype "passive"))
      (node (ref "R3") (pin "2") (pinfunction "2_2") (pintype "passive"))
      (node (ref "R4") (pin "2") (pinfunction "2_2") (pintype "passive"))
      (node (ref "Z3") (pin "K") (pinfunction "K_K") (pintype "passive"))
      (node (ref "Z4") (pin "K") (pinfunction "K_K") (pintype "passive"))
    )
    (net (code "67") (name "VpCh2") (class "Default")
      (node (ref "Q1") (pin "1") (pinfunction "S1_1") (pintype "passive"))
      (node (ref "Q1") (pin "3") (pinfunction "S2_3") (pintype "passive"))
      (node (ref "R1") (pin "2") (pinfunction "2_2") (pintype "passive"))
      (node (ref "R2") (pin "2") (pinfunction "2_2") (pintype "passive"))
      (node (ref "Z1") (pin "K") (pinfunction "K_K") (pintype "passive"))
      (node (ref "Z2") (pin "K") (pinfunction "K_K") (pintype "passive"))
    )
  )
)
